# KNX-RELAY-24CH_V0_2.net
KiCad netlist of a schematic drawn in Altium Designer
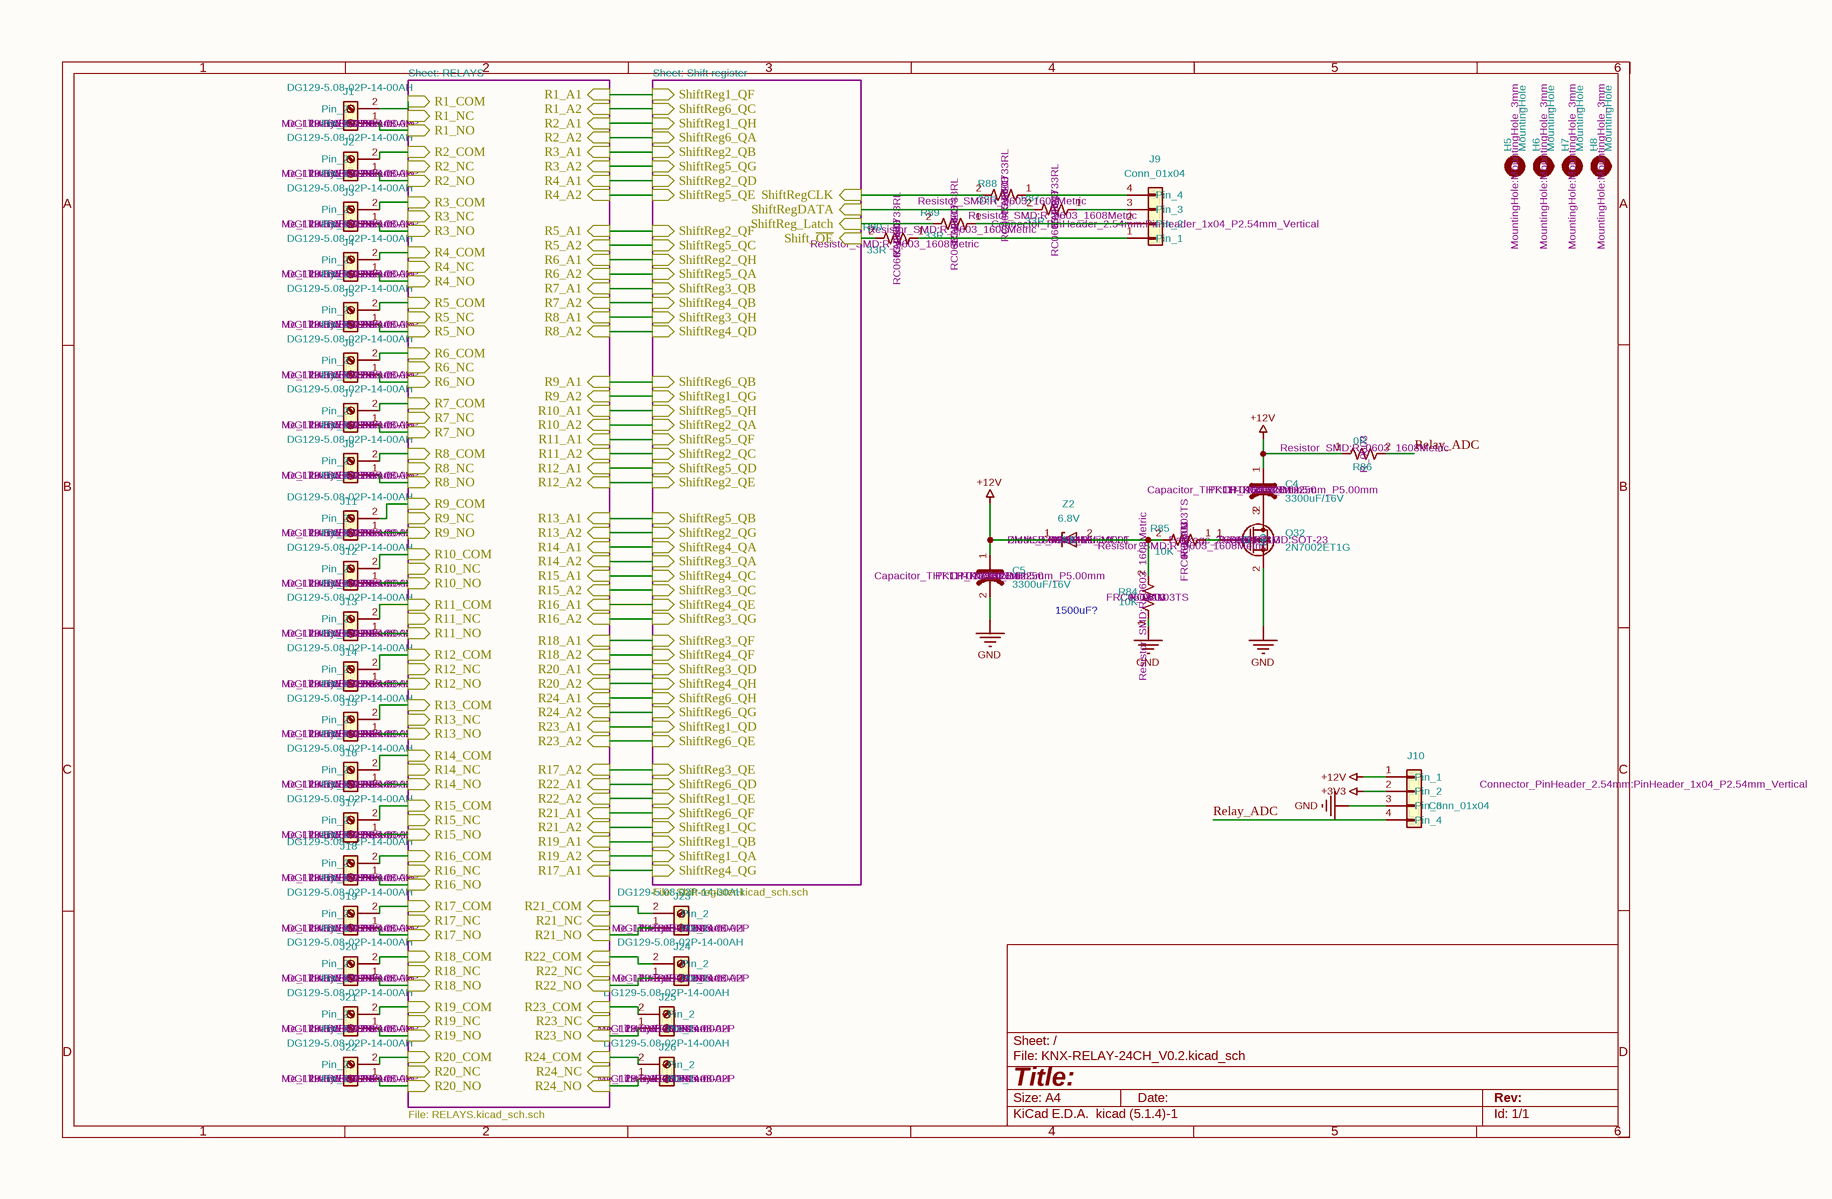
[diagram p0: KNX-RELAY-24CH_V0.2.SchDoc]

(export (version "E")
  (design (tool "Eeschema 10.0.6"))
  (components
    (comp (ref "C4")
      (value "3300uF/16V")
      (footprint "Capacitor_THT:CP_Radial_D12.5mm_P5.00mm")
      (fields
        (field (name "MANUFACTURER PART NUMBER") "PKLH-016V332MH250")
        (field (name "MANUFACTURER") "KOSHIN")
        (field (name "PACKAGE") "THT 12.5x25mm")
      )
      (libsource (lib "Device") (part "C_US"))
    )
    (comp (ref "C5")
      (value "3300uF/16V")
      (footprint "Capacitor_THT:CP_Radial_D12.5mm_P5.00mm")
      (fields
        (field (name "MANUFACTURER PART NUMBER") "PKLH-016V332MH250")
        (field (name "MANUFACTURER") "KOSHIN")
        (field (name "PACKAGE") "THT 12.5x25mm")
      )
      (libsource (lib "Device") (part "C_US"))
    )
    (comp (ref "H5")
      (value "MountingHole")
      (footprint "MountingHole:MountingHole_3mm")
      (libsource (lib "Mechanical") (part "MountingHole"))
    )
    (comp (ref "H6")
      (value "MountingHole")
      (footprint "MountingHole:MountingHole_3mm")
      (libsource (lib "Mechanical") (part "MountingHole"))
    )
    (comp (ref "H7")
      (value "MountingHole")
      (footprint "MountingHole:MountingHole_3mm")
      (libsource (lib "Mechanical") (part "MountingHole"))
    )
    (comp (ref "H8")
      (value "MountingHole")
      (footprint "MountingHole:MountingHole_3mm")
      (libsource (lib "Mechanical") (part "MountingHole"))
    )
    (comp (ref "J1")
      (value "DG129-5.08-02P-14-00AH")
      (footprint "Me_Library:DG129-5.08-02P")
      (fields
        (field (name "MANUFACTURER PART NUMBER") "DG129-5.08-02P-14-00AH")
        (field (name "MANUFACTURER") "DEGSON")
        (field (name "PACKAGE") "THT V/T  5.08mm")
      )
      (libsource (lib "Connector") (part "Screw_Terminal_01x02"))
    )
    (comp (ref "J2")
      (value "DG129-5.08-02P-14-00AH")
      (footprint "Me_Library:DG129-5.08-02P")
      (fields
        (field (name "MANUFACTURER PART NUMBER") "DG129-5.08-02P-14-00AH")
        (field (name "MANUFACTURER") "DEGSON")
        (field (name "PACKAGE") "THT V/T  5.08mm")
      )
      (libsource (lib "Connector") (part "Screw_Terminal_01x02"))
    )
    (comp (ref "J3")
      (value "DG129-5.08-02P-14-00AH")
      (footprint "Me_Library:DG129-5.08-02P")
      (fields
        (field (name "MANUFACTURER PART NUMBER") "DG129-5.08-02P-14-00AH")
        (field (name "MANUFACTURER") "DEGSON")
        (field (name "PACKAGE") "THT V/T  5.08mm")
      )
      (libsource (lib "Connector") (part "Screw_Terminal_01x02"))
    )
    (comp (ref "J4")
      (value "DG129-5.08-02P-14-00AH")
      (footprint "Me_Library:DG129-5.08-02P")
      (fields
        (field (name "MANUFACTURER PART NUMBER") "DG129-5.08-02P-14-00AH")
        (field (name "MANUFACTURER") "DEGSON")
        (field (name "PACKAGE") "THT V/T  5.08mm")
      )
      (libsource (lib "Connector") (part "Screw_Terminal_01x02"))
    )
    (comp (ref "J5")
      (value "DG129-5.08-02P-14-00AH")
      (footprint "Me_Library:DG129-5.08-02P")
      (fields
        (field (name "MANUFACTURER PART NUMBER") "DG129-5.08-02P-14-00AH")
        (field (name "MANUFACTURER") "DEGSON")
        (field (name "PACKAGE") "THT V/T  5.08mm")
      )
      (libsource (lib "Connector") (part "Screw_Terminal_01x02"))
    )
    (comp (ref "J6")
      (value "DG129-5.08-02P-14-00AH")
      (footprint "Me_Library:DG129-5.08-02P")
      (fields
        (field (name "MANUFACTURER PART NUMBER") "DG129-5.08-02P-14-00AH")
        (field (name "MANUFACTURER") "DEGSON")
        (field (name "PACKAGE") "THT V/T  5.08mm")
      )
      (libsource (lib "Connector") (part "Screw_Terminal_01x02"))
    )
    (comp (ref "J7")
      (value "DG129-5.08-02P-14-00AH")
      (footprint "Me_Library:DG129-5.08-02P")
      (fields
        (field (name "MANUFACTURER PART NUMBER") "DG129-5.08-02P-14-00AH")
        (field (name "MANUFACTURER") "DEGSON")
        (field (name "PACKAGE") "THT V/T  5.08mm")
      )
      (libsource (lib "Connector") (part "Screw_Terminal_01x02"))
    )
    (comp (ref "J8")
      (value "DG129-5.08-02P-14-00AH")
      (footprint "Me_Library:DG129-5.08-02P")
      (fields
        (field (name "MANUFACTURER PART NUMBER") "DG129-5.08-02P-14-00AH")
        (field (name "MANUFACTURER") "DEGSON")
        (field (name "PACKAGE") "THT V/T  5.08mm")
      )
      (libsource (lib "Connector") (part "Screw_Terminal_01x02"))
    )
    (comp (ref "J9")
      (value "Conn_01x04")
      (footprint "Connector_PinHeader_2.54mm:PinHeader_1x04_P2.54mm_Vertical")
      (description "FEMALE HEADER 4PIN(1x4) 2.54mm THT V/T TRAY")
      (fields
        (field (name "MANUFACTURER PART NUMBER") "5PS1SDA85-104G0NNNAL-00")
        (field (name "MANUFACTURER") "AMTEK")
      )
      (libsource (lib "") (part "Conn_01x04_1"))
    )
    (comp (ref "J10")
      (value "Conn_01x04")
      (footprint "Connector_PinHeader_2.54mm:PinHeader_1x04_P2.54mm_Vertical")
      (description "FEMALE HEADER 4PIN(1x4) 2.54mm THT V/T TRAY")
      (fields
        (field (name "MANUFACTURER PART NUMBER") "5PS1SDA85-104G0NNNAL-00")
        (field (name "MANUFACTURER") "AMTEK")
      )
      (libsource (lib "Connector_Generic") (part "Conn_01x04"))
    )
    (comp (ref "J11")
      (value "DG129-5.08-02P-14-00AH")
      (footprint "Me_Library:DG129-5.08-02P")
      (fields
        (field (name "MANUFACTURER PART NUMBER") "DG129-5.08-02P-14-00AH")
        (field (name "MANUFACTURER") "DEGSON")
        (field (name "PACKAGE") "THT V/T  5.08mm")
      )
      (libsource (lib "Connector") (part "Screw_Terminal_01x02"))
    )
    (comp (ref "J12")
      (value "DG129-5.08-02P-14-00AH")
      (footprint "Me_Library:DG129-5.08-02P")
      (fields
        (field (name "MANUFACTURER PART NUMBER") "DG129-5.08-02P-14-00AH")
        (field (name "MANUFACTURER") "DEGSON")
        (field (name "PACKAGE") "THT V/T  5.08mm")
      )
      (libsource (lib "Connector") (part "Screw_Terminal_01x02"))
    )
    (comp (ref "J13")
      (value "DG129-5.08-02P-14-00AH")
      (footprint "Me_Library:DG129-5.08-02P")
      (fields
        (field (name "MANUFACTURER PART NUMBER") "DG129-5.08-02P-14-00AH")
        (field (name "MANUFACTURER") "DEGSON")
        (field (name "PACKAGE") "THT V/T  5.08mm")
      )
      (libsource (lib "Connector") (part "Screw_Terminal_01x02"))
    )
    (comp (ref "J14")
      (value "DG129-5.08-02P-14-00AH")
      (footprint "Me_Library:DG129-5.08-02P")
      (fields
        (field (name "MANUFACTURER PART NUMBER") "DG129-5.08-02P-14-00AH")
        (field (name "MANUFACTURER") "DEGSON")
        (field (name "PACKAGE") "THT V/T  5.08mm")
      )
      (libsource (lib "Connector") (part "Screw_Terminal_01x02"))
    )
    (comp (ref "J15")
      (value "DG129-5.08-02P-14-00AH")
      (footprint "Me_Library:DG129-5.08-02P")
      (fields
        (field (name "MANUFACTURER PART NUMBER") "DG129-5.08-02P-14-00AH")
        (field (name "MANUFACTURER") "DEGSON")
        (field (name "PACKAGE") "THT V/T  5.08mm")
      )
      (libsource (lib "Connector") (part "Screw_Terminal_01x02"))
    )
    (comp (ref "J16")
      (value "DG129-5.08-02P-14-00AH")
      (footprint "Me_Library:DG129-5.08-02P")
      (fields
        (field (name "MANUFACTURER PART NUMBER") "DG129-5.08-02P-14-00AH")
        (field (name "MANUFACTURER") "DEGSON")
        (field (name "PACKAGE") "THT V/T  5.08mm")
      )
      (libsource (lib "Connector") (part "Screw_Terminal_01x02"))
    )
    (comp (ref "J17")
      (value "DG129-5.08-02P-14-00AH")
      (footprint "Me_Library:DG129-5.08-02P")
      (fields
        (field (name "MANUFACTURER PART NUMBER") "DG129-5.08-02P-14-00AH")
        (field (name "MANUFACTURER") "DEGSON")
        (field (name "PACKAGE") "THT V/T  5.08mm")
      )
      (libsource (lib "Connector") (part "Screw_Terminal_01x02"))
    )
    (comp (ref "J18")
      (value "DG129-5.08-02P-14-00AH")
      (footprint "Me_Library:DG129-5.08-02P")
      (fields
        (field (name "MANUFACTURER PART NUMBER") "DG129-5.08-02P-14-00AH")
        (field (name "MANUFACTURER") "DEGSON")
        (field (name "PACKAGE") "THT V/T  5.08mm")
      )
      (libsource (lib "Connector") (part "Screw_Terminal_01x02"))
    )
    (comp (ref "J19")
      (value "DG129-5.08-02P-14-00AH")
      (footprint "Me_Library:DG129-5.08-02P")
      (fields
        (field (name "MANUFACTURER PART NUMBER") "DG129-5.08-02P-14-00AH")
        (field (name "MANUFACTURER") "DEGSON")
        (field (name "PACKAGE") "THT V/T  5.08mm")
      )
      (libsource (lib "Connector") (part "Screw_Terminal_01x02"))
    )
    (comp (ref "J20")
      (value "DG129-5.08-02P-14-00AH")
      (footprint "Me_Library:DG129-5.08-02P")
      (fields
        (field (name "MANUFACTURER PART NUMBER") "DG129-5.08-02P-14-00AH")
        (field (name "MANUFACTURER") "DEGSON")
        (field (name "PACKAGE") "THT V/T  5.08mm")
      )
      (libsource (lib "Connector") (part "Screw_Terminal_01x02"))
    )
    (comp (ref "J21")
      (value "DG129-5.08-02P-14-00AH")
      (footprint "Me_Library:DG129-5.08-02P")
      (fields
        (field (name "MANUFACTURER PART NUMBER") "DG129-5.08-02P-14-00AH")
        (field (name "MANUFACTURER") "DEGSON")
        (field (name "PACKAGE") "THT V/T  5.08mm")
      )
      (libsource (lib "Connector") (part "Screw_Terminal_01x02"))
    )
    (comp (ref "J22")
      (value "DG129-5.08-02P-14-00AH")
      (footprint "Me_Library:DG129-5.08-02P")
      (fields
        (field (name "MANUFACTURER PART NUMBER") "DG129-5.08-02P-14-00AH")
        (field (name "MANUFACTURER") "DEGSON")
        (field (name "PACKAGE") "THT V/T  5.08mm")
      )
      (libsource (lib "Connector") (part "Screw_Terminal_01x02"))
    )
    (comp (ref "J23")
      (value "DG129-5.08-02P-14-00AH")
      (footprint "Me_Library:DG129-5.08-02P")
      (fields
        (field (name "MANUFACTURER PART NUMBER") "DG129-5.08-02P-14-00AH")
        (field (name "MANUFACTURER") "DEGSON")
        (field (name "PACKAGE") "THT V/T  5.08mm")
      )
      (libsource (lib "") (part "Screw_Terminal_01x02_1"))
    )
    (comp (ref "J24")
      (value "DG129-5.08-02P-14-00AH")
      (footprint "Me_Library:DG129-5.08-02P")
      (fields
        (field (name "MANUFACTURER PART NUMBER") "DG129-5.08-02P-14-00AH")
        (field (name "MANUFACTURER") "DEGSON")
        (field (name "PACKAGE") "THT V/T  5.08mm")
      )
      (libsource (lib "") (part "Screw_Terminal_01x02_1"))
    )
    (comp (ref "J25")
      (value "DG129-5.08-02P-14-00AH")
      (footprint "Me_Library:DG129-5.08-02P")
      (fields
        (field (name "MANUFACTURER PART NUMBER") "DG129-5.08-02P-14-00AH")
        (field (name "MANUFACTURER") "DEGSON")
        (field (name "PACKAGE") "THT V/T  5.08mm")
      )
      (libsource (lib "") (part "Screw_Terminal_01x02_1"))
    )
    (comp (ref "J26")
      (value "DG129-5.08-02P-14-00AH")
      (footprint "Me_Library:DG129-5.08-02P")
      (fields
        (field (name "MANUFACTURER PART NUMBER") "DG129-5.08-02P-14-00AH")
        (field (name "MANUFACTURER") "DEGSON")
        (field (name "PACKAGE") "THT V/T  5.08mm")
      )
      (libsource (lib "") (part "Screw_Terminal_01x02_1"))
    )
    (comp (ref "Q32")
      (value "2N7002ET1G")
      (footprint "Package_TO_SOT_SMD:SOT-23")
      (fields
        (field (name "MANUFACTURER PART NUMBER") "2N7002ET1G")
        (field (name "MANUFACTURER") "onsemi")
        (field (name "PACKAGE") "SOT-23")
      )
      (libsource (lib "Transistor_FET_Other") (part "Q_NMOS_Depletion_GSD"))
    )
    (comp (ref "R84")
      (value "10K")
      (footprint "Resistor_SMD:R_0603_1608Metric")
      (fields
        (field (name "MANUFACTURER PART NUMBER") "FRC0603J103TS")
        (field (name "MANUFACTURER") "FOJAN")
        (field (name "PACKAGE") "R_0603")
      )
      (libsource (lib "Device") (part "R_US"))
    )
    (comp (ref "R85")
      (value "10K")
      (footprint "Resistor_SMD:R_0603_1608Metric")
      (fields
        (field (name "MANUFACTURER PART NUMBER") "FRC0603J103TS")
        (field (name "MANUFACTURER") "FOJAN")
        (field (name "PACKAGE") "R_0603")
      )
      (libsource (lib "Device") (part "R_US"))
    )
    (comp (ref "R86")
      (value "0R")
      (footprint "Resistor_SMD:R_0603_1608Metric")
      (description "RES.(1608) 0603 0 Ohms 1/10W JUMPER")
      (fields
        (field (name "PACKAGE") "R_0603")
        (field (name "MANUFACTURER PART NUMBER") "ERJ3GEY0R00V")
        (field (name "MANUFACTURER") "PANASONIC(EUROPE)")
      )
      (libsource (lib "Device") (part "R_US"))
    )
    (comp (ref "R87")
      (value "33R")
      (footprint "Resistor_SMD:R_0603_1608Metric")
      (fields
        (field (name "MANUFACTURER PART NUMBER") "RC0603JR-0733RL")
        (field (name "MANUFACTURER") "YAGEO")
        (field (name "PACKAGE") "R_0603")
      )
      (libsource (lib "Device") (part "R_US"))
    )
    (comp (ref "R88")
      (value "33R")
      (footprint "Resistor_SMD:R_0603_1608Metric")
      (fields
        (field (name "MANUFACTURER PART NUMBER") "RC0603JR-0733RL")
        (field (name "MANUFACTURER") "YAGEO")
        (field (name "PACKAGE") "R_0603")
      )
      (libsource (lib "Device") (part "R_US"))
    )
    (comp (ref "R89")
      (value "33R")
      (footprint "Resistor_SMD:R_0603_1608Metric")
      (fields
        (field (name "MANUFACTURER PART NUMBER") "RC0603JR-0733RL")
        (field (name "MANUFACTURER") "YAGEO")
        (field (name "PACKAGE") "R_0603")
      )
      (libsource (lib "Device") (part "R_US"))
    )
    (comp (ref "R90")
      (value "33R")
      (footprint "Resistor_SMD:R_0603_1608Metric")
      (fields
        (field (name "MANUFACTURER PART NUMBER") "RC0603JR-0733RL")
        (field (name "MANUFACTURER") "YAGEO")
        (field (name "PACKAGE") "R_0603")
      )
      (libsource (lib "Device") (part "R_US"))
    )
    (comp (ref "Z2")
      (value "6.8V")
      (footprint "Diode_SMD:D_MiniMELF")
      (fields
        (field (name "MANUFACTURER PART NUMBER") "ZMM55-C6V8_R1_10001")
        (field (name "MANUFACTURER") "PANJIT")
        (field (name "PACKAGE") "D_MiniMELF")
      )
      (libsource (lib "Device") (part "D_Zener"))
    )
  )
  (nets
    (net (code "1") (name "+3V3") (class "Default")
      (node (ref "J10") (pin "2") (pinfunction "Pin_2_2") (pintype "passive"))
    )
    (net (code "2") (name "+12V") (class "Default")
      (node (ref "C4") (pin "1") (pinfunction "1_1") (pintype "passive"))
      (node (ref "C5") (pin "1") (pinfunction "1_1") (pintype "passive"))
      (node (ref "J10") (pin "1") (pinfunction "Pin_1_1") (pintype "passive"))
      (node (ref "R86") (pin "1") (pinfunction "1_1") (pintype "passive"))
      (node (ref "Z2") (pin "1") (pinfunction "K_1") (pintype "passive"))
    )
    (net (code "5") (name "/R1_COM") (class "Default")
      (node (ref "J1") (pin "2") (pinfunction "Pin_2_2") (pintype "passive"))
    )
    (net (code "7") (name "/R1_NO") (class "Default")
      (node (ref "J1") (pin "1") (pinfunction "Pin_1_1") (pintype "passive"))
    )
    (net (code "10") (name "/R2_COM") (class "Default")
      (node (ref "J2") (pin "2") (pinfunction "Pin_2_2") (pintype "passive"))
    )
    (net (code "12") (name "/R2_NO") (class "Default")
      (node (ref "J2") (pin "1") (pinfunction "Pin_1_1") (pintype "passive"))
    )
    (net (code "15") (name "/R3_COM") (class "Default")
      (node (ref "J3") (pin "2") (pinfunction "Pin_2_2") (pintype "passive"))
    )
    (net (code "17") (name "/R3_NO") (class "Default")
      (node (ref "J3") (pin "1") (pinfunction "Pin_1_1") (pintype "passive"))
    )
    (net (code "20") (name "/R4_COM") (class "Default")
      (node (ref "J4") (pin "2") (pinfunction "Pin_2_2") (pintype "passive"))
    )
    (net (code "22") (name "/R4_NO") (class "Default")
      (node (ref "J4") (pin "1") (pinfunction "Pin_1_1") (pintype "passive"))
    )
    (net (code "25") (name "/R5_COM") (class "Default")
      (node (ref "J5") (pin "2") (pinfunction "Pin_2_2") (pintype "passive"))
    )
    (net (code "27") (name "/R5_NO") (class "Default")
      (node (ref "J5") (pin "1") (pinfunction "Pin_1_1") (pintype "passive"))
    )
    (net (code "30") (name "/R6_COM") (class "Default")
      (node (ref "J6") (pin "2") (pinfunction "Pin_2_2") (pintype "passive"))
    )
    (net (code "32") (name "/R6_NO") (class "Default")
      (node (ref "J6") (pin "1") (pinfunction "Pin_1_1") (pintype "passive"))
    )
    (net (code "35") (name "/R7_COM") (class "Default")
      (node (ref "J7") (pin "2") (pinfunction "Pin_2_2") (pintype "passive"))
    )
    (net (code "37") (name "/R7_NO") (class "Default")
      (node (ref "J7") (pin "1") (pinfunction "Pin_1_1") (pintype "passive"))
    )
    (net (code "40") (name "/R8_COM") (class "Default")
      (node (ref "J8") (pin "2") (pinfunction "Pin_2_2") (pintype "passive"))
    )
    (net (code "42") (name "/R8_NO") (class "Default")
      (node (ref "J8") (pin "1") (pinfunction "Pin_1_1") (pintype "passive"))
    )
    (net (code "45") (name "/R9_COM") (class "Default")
      (node (ref "J11") (pin "2") (pinfunction "Pin_2_2") (pintype "passive"))
    )
    (net (code "47") (name "/R9_NO") (class "Default")
      (node (ref "J11") (pin "1") (pinfunction "Pin_1_1") (pintype "passive"))
    )
    (net (code "50") (name "/R10_COM") (class "Default")
      (node (ref "J12") (pin "2") (pinfunction "Pin_2_2") (pintype "passive"))
    )
    (net (code "52") (name "/R10_NO") (class "Default")
      (node (ref "J12") (pin "1") (pinfunction "Pin_1_1") (pintype "passive"))
    )
    (net (code "55") (name "/R11_COM") (class "Default")
      (node (ref "J13") (pin "2") (pinfunction "Pin_2_2") (pintype "passive"))
    )
    (net (code "57") (name "/R11_NO") (class "Default")
      (node (ref "J13") (pin "1") (pinfunction "Pin_1_1") (pintype "passive"))
    )
    (net (code "60") (name "/R12_COM") (class "Default")
      (node (ref "J14") (pin "2") (pinfunction "Pin_2_2") (pintype "passive"))
    )
    (net (code "62") (name "/R12_NO") (class "Default")
      (node (ref "J14") (pin "1") (pinfunction "Pin_1_1") (pintype "passive"))
    )
    (net (code "65") (name "/R13_COM") (class "Default")
      (node (ref "J15") (pin "2") (pinfunction "Pin_2_2") (pintype "passive"))
    )
    (net (code "67") (name "/R13_NO") (class "Default")
      (node (ref "J15") (pin "1") (pinfunction "Pin_1_1") (pintype "passive"))
    )
    (net (code "70") (name "/R14_COM") (class "Default")
      (node (ref "J16") (pin "2") (pinfunction "Pin_2_2") (pintype "passive"))
    )
    (net (code "72") (name "/R14_NO") (class "Default")
      (node (ref "J16") (pin "1") (pinfunction "Pin_1_1") (pintype "passive"))
    )
    (net (code "75") (name "/R15_COM") (class "Default")
      (node (ref "J17") (pin "2") (pinfunction "Pin_2_2") (pintype "passive"))
    )
    (net (code "77") (name "/R15_NO") (class "Default")
      (node (ref "J17") (pin "1") (pinfunction "Pin_1_1") (pintype "passive"))
    )
    (net (code "80") (name "/R16_COM") (class "Default")
      (node (ref "J18") (pin "2") (pinfunction "Pin_2_2") (pintype "passive"))
    )
    (net (code "82") (name "/R16_NO") (class "Default")
      (node (ref "J18") (pin "1") (pinfunction "Pin_1_1") (pintype "passive"))
    )
    (net (code "85") (name "/R17_COM") (class "Default")
      (node (ref "J19") (pin "2") (pinfunction "Pin_2_2") (pintype "passive"))
    )
    (net (code "87") (name "/R17_NO") (class "Default")
      (node (ref "J19") (pin "1") (pinfunction "Pin_1_1") (pintype "passive"))
    )
    (net (code "90") (name "/R18_COM") (class "Default")
      (node (ref "J20") (pin "2") (pinfunction "Pin_2_2") (pintype "passive"))
    )
    (net (code "92") (name "/R18_NO") (class "Default")
      (node (ref "J20") (pin "1") (pinfunction "Pin_1_1") (pintype "passive"))
    )
    (net (code "95") (name "/R19_COM") (class "Default")
      (node (ref "J21") (pin "2") (pinfunction "Pin_2_2") (pintype "passive"))
    )
    (net (code "97") (name "/R19_NO") (class "Default")
      (node (ref "J21") (pin "1") (pinfunction "Pin_1_1") (pintype "passive"))
    )
    (net (code "100") (name "/R20_COM") (class "Default")
      (node (ref "J22") (pin "2") (pinfunction "Pin_2_2") (pintype "passive"))
    )
    (net (code "102") (name "/R20_NO") (class "Default")
      (node (ref "J22") (pin "1") (pinfunction "Pin_1_1") (pintype "passive"))
    )
    (net (code "105") (name "/R21_COM") (class "Default")
      (node (ref "J23") (pin "2") (pinfunction "Pin_2_2") (pintype "passive"))
    )
    (net (code "107") (name "/R21_NO") (class "Default")
      (node (ref "J23") (pin "1") (pinfunction "Pin_1_1") (pintype "passive"))
    )
    (net (code "110") (name "/R22_COM") (class "Default")
      (node (ref "J24") (pin "2") (pinfunction "Pin_2_2") (pintype "passive"))
    )
    (net (code "112") (name "/R22_NO") (class "Default")
      (node (ref "J24") (pin "1") (pinfunction "Pin_1_1") (pintype "passive"))
    )
    (net (code "115") (name "/R23_COM") (class "Default")
      (node (ref "J25") (pin "2") (pinfunction "Pin_2_2") (pintype "passive"))
    )
    (net (code "117") (name "/R23_NO") (class "Default")
      (node (ref "J25") (pin "1") (pinfunction "Pin_1_1") (pintype "passive"))
    )
    (net (code "120") (name "/R24_COM") (class "Default")
      (node (ref "J26") (pin "2") (pinfunction "Pin_2_2") (pintype "passive"))
    )
    (net (code "122") (name "/R24_NO") (class "Default")
      (node (ref "J26") (pin "1") (pinfunction "Pin_1_1") (pintype "passive"))
    )
    (net (code "123") (name "/Relay_ADC") (class "Default")
      (node (ref "J10") (pin "4") (pinfunction "Pin_4_4") (pintype "passive"))
      (node (ref "R86") (pin "2") (pinfunction "2_2") (pintype "passive"))
    )
    (net (code "124") (name "/ShiftRegCLK") (class "Default")
      (node (ref "R88") (pin "2") (pinfunction "2_2") (pintype "passive"))
    )
    (net (code "125") (name "/ShiftRegDATA") (class "Default")
      (node (ref "R87") (pin "2") (pinfunction "2_2") (pintype "passive"))
    )
    (net (code "126") (name "/ShiftReg_Latch") (class "Default")
      (node (ref "R89") (pin "2") (pinfunction "2_2") (pintype "passive"))
    )
    (net (code "127") (name "/Shift_~{OE}") (class "Default")
      (node (ref "R90") (pin "2") (pinfunction "2_2") (pintype "passive"))
    )
    (net (code "128") (name "GND") (class "Default")
      (node (ref "C5") (pin "2") (pinfunction "2_2") (pintype "passive"))
      (node (ref "J10") (pin "3") (pinfunction "Pin_3_3") (pintype "passive"))
      (node (ref "Q32") (pin "2") (pinfunction "S_2") (pintype "passive"))
      (node (ref "R84") (pin "1") (pinfunction "1_1") (pintype "passive"))
    )
    (net (code "129") (name "Net-(J9-Pin_1)") (class "Default")
      (node (ref "J9") (pin "1") (pinfunction "Pin_1_1") (pintype "passive"))
      (node (ref "R90") (pin "1") (pinfunction "1_1") (pintype "passive"))
    )
    (net (code "130") (name "Net-(J9-Pin_2)") (class "Default")
      (node (ref "J9") (pin "2") (pinfunction "Pin_2_2") (pintype "passive"))
      (node (ref "R89") (pin "1") (pinfunction "1_1") (pintype "passive"))
    )
    (net (code "131") (name "Net-(J9-Pin_3)") (class "Default")
      (node (ref "J9") (pin "3") (pinfunction "Pin_3_3") (pintype "passive"))
      (node (ref "R87") (pin "1") (pinfunction "1_1") (pintype "passive"))
    )
    (net (code "132") (name "Net-(J9-Pin_4)") (class "Default")
      (node (ref "J9") (pin "4") (pinfunction "Pin_4_4") (pintype "passive"))
      (node (ref "R88") (pin "1") (pinfunction "1_1") (pintype "passive"))
    )
    (net (code "133") (name "Net-(Q32-D)") (class "Default")
      (node (ref "C4") (pin "2") (pinfunction "2_2") (pintype "passive"))
      (node (ref "Q32") (pin "3") (pinfunction "D_3") (pintype "passive"))
    )
    (net (code "134") (name "Net-(Q32-G)") (class "Default")
      (node (ref "Q32") (pin "1") (pinfunction "G_1") (pintype "passive"))
      (node (ref "R85") (pin "1") (pinfunction "1_1") (pintype "passive"))
    )
    (net (code "135") (name "Net-(Z2-A)") (class "Default")
      (node (ref "R84") (pin "2") (pinfunction "2_2") (pintype "passive"))
      (node (ref "R85") (pin "2") (pinfunction "2_2") (pintype "passive"))
      (node (ref "Z2") (pin "2") (pinfunction "A_2") (pintype "passive"))
    )
  )
)
